# Laser_Sign_Remote.net
KiCad netlist of a schematic drawn in EasyEDA
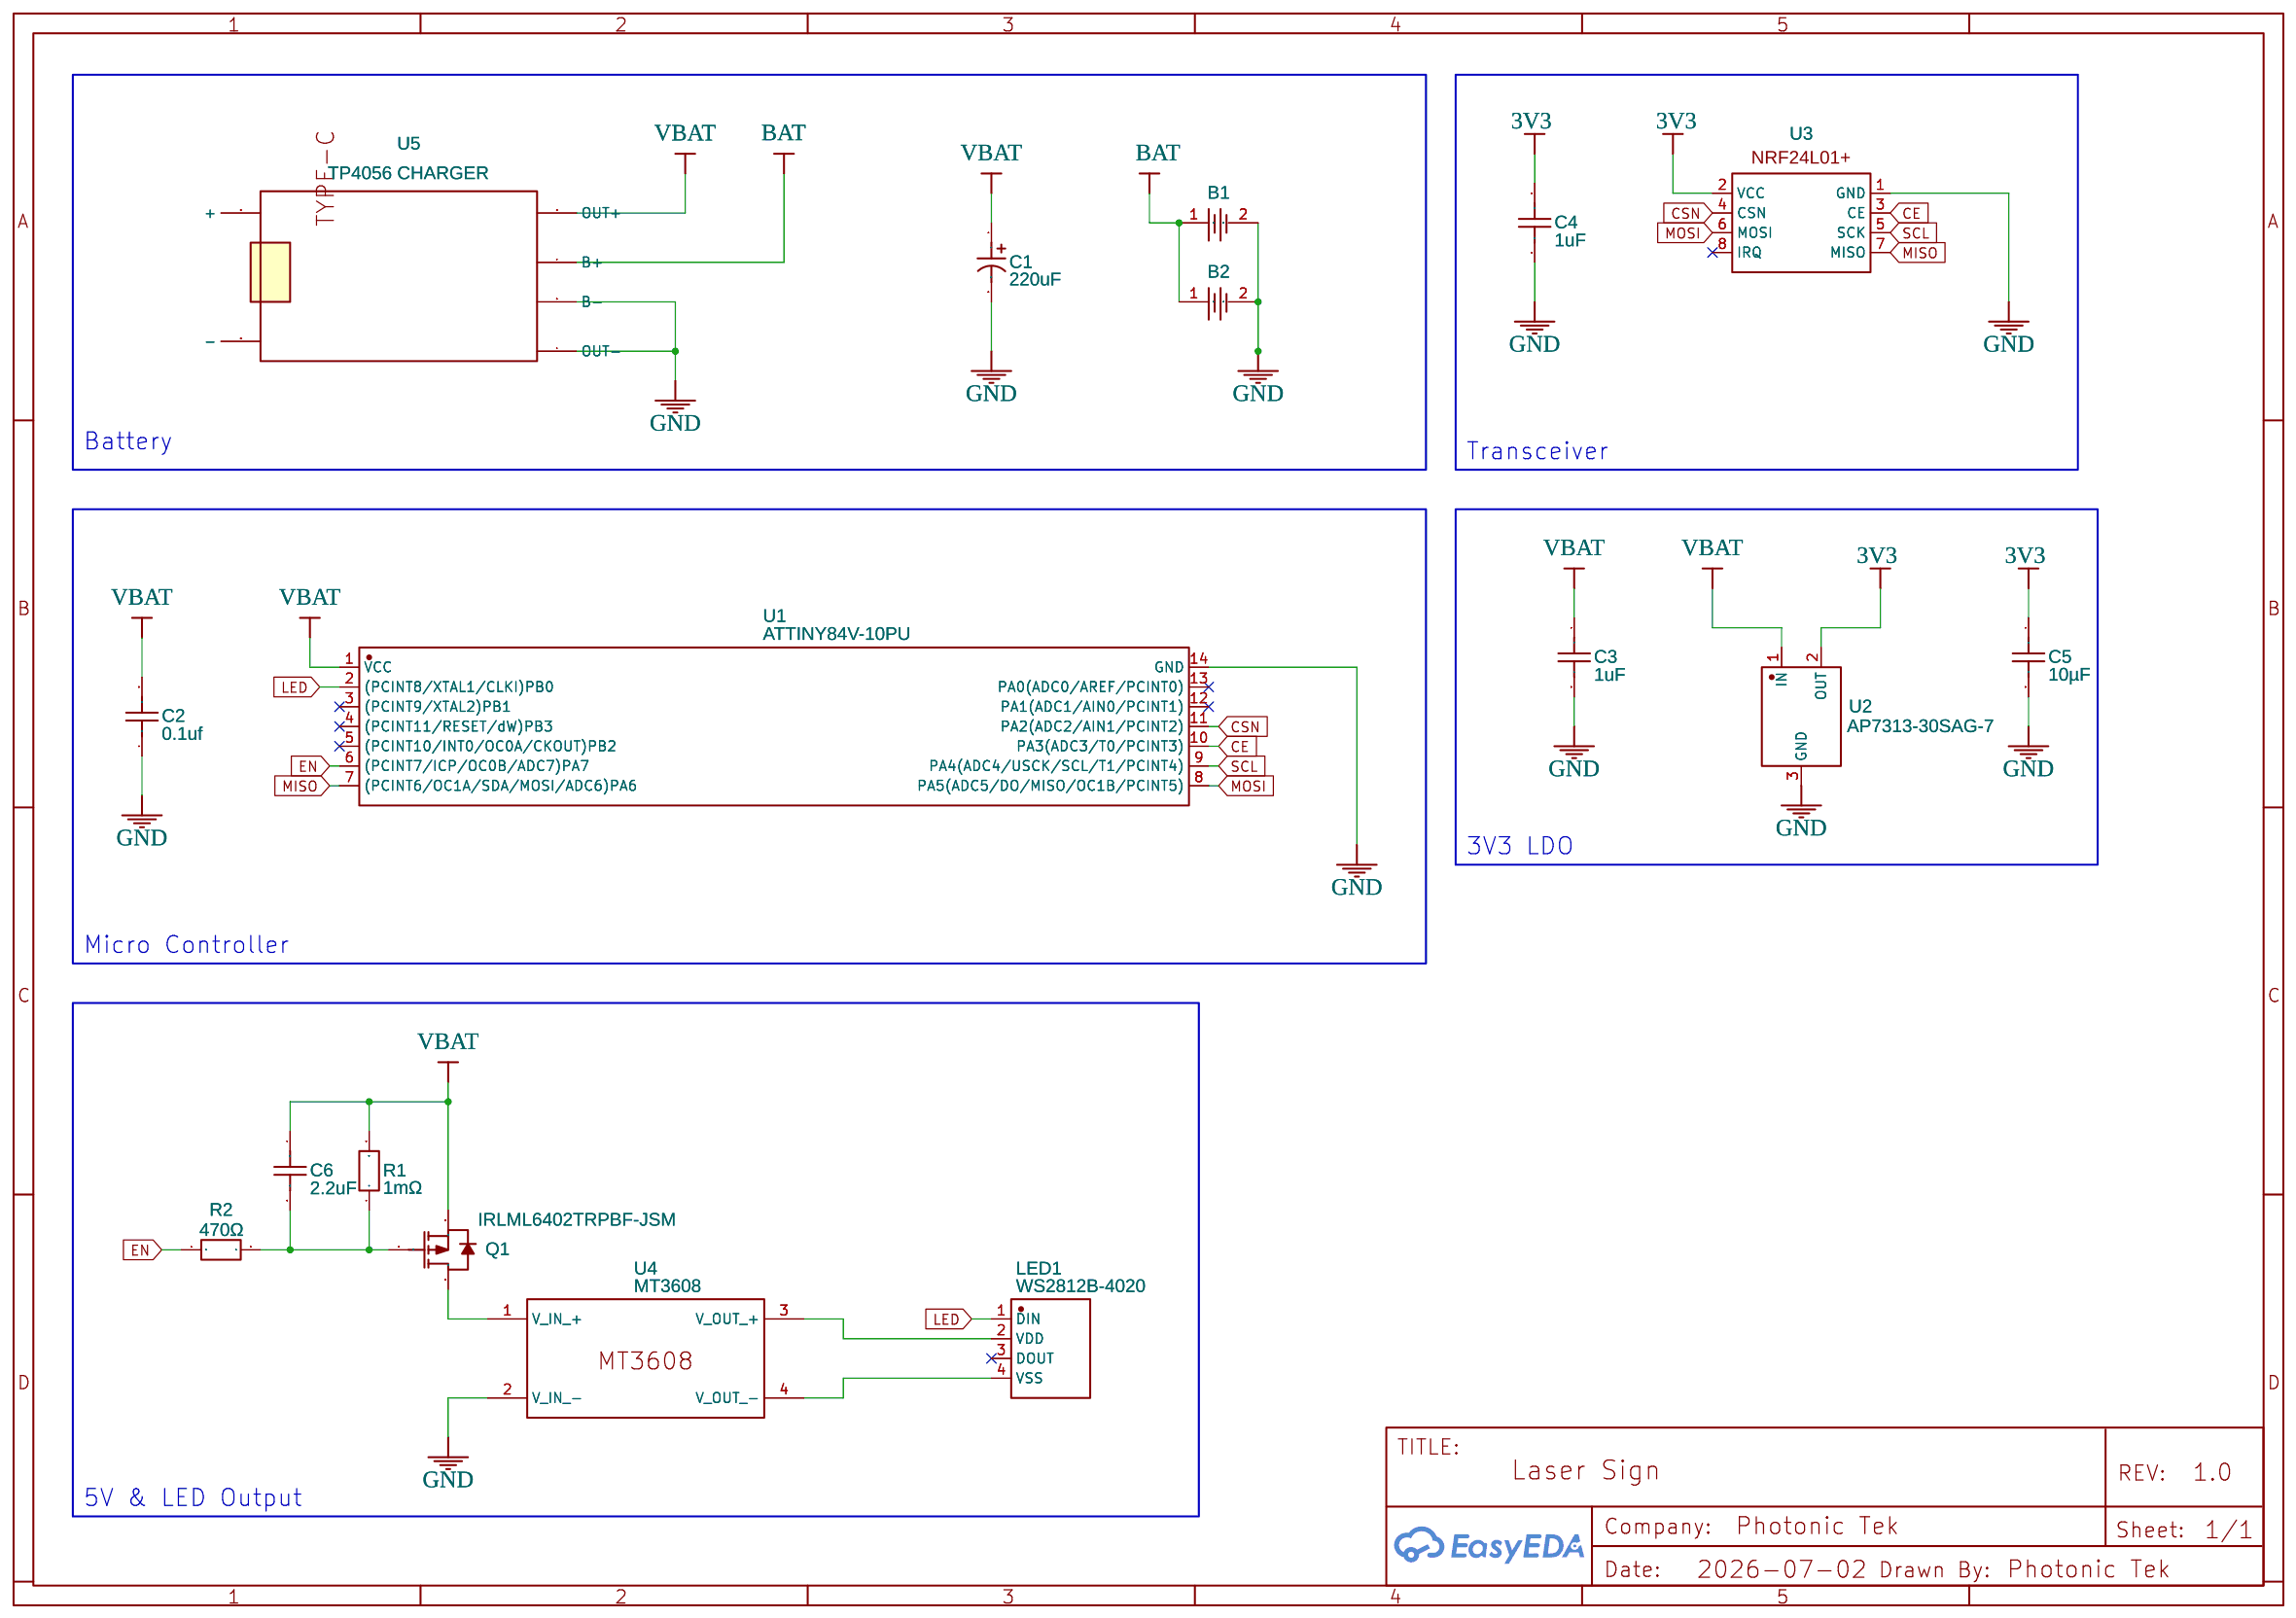
[diagram p0: Sheet_1]
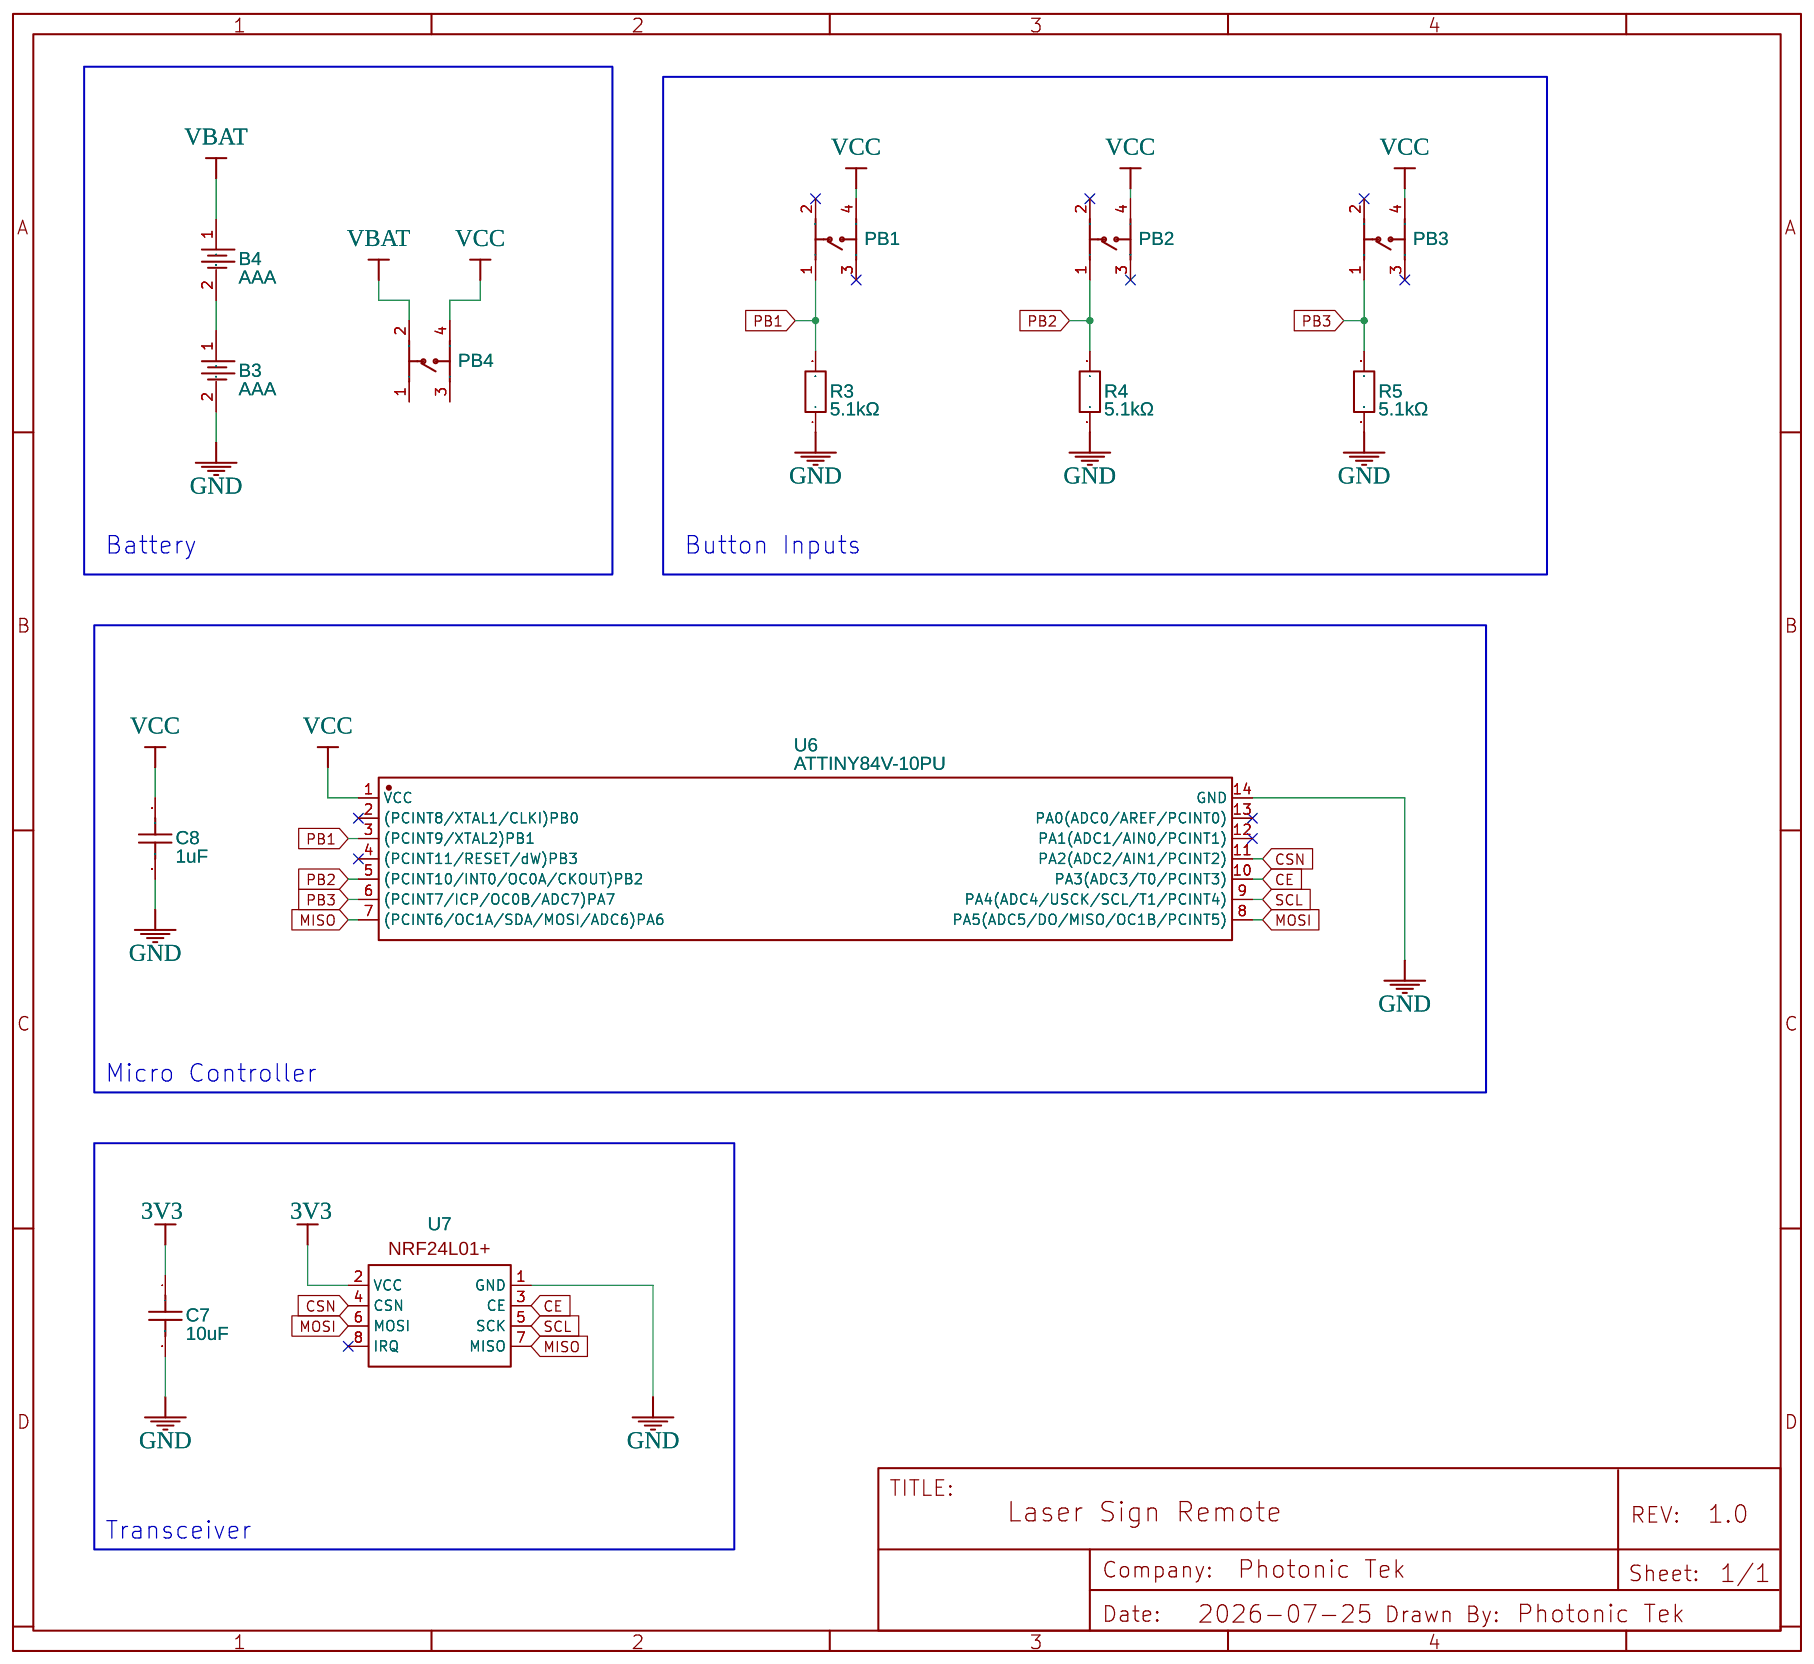
[diagram p1: Sheet_2]

(export (version "E")
  (design (tool "Eeschema 10.0.6"))
  (components
    (comp (ref "B1")
      (value "CR1220-2")
      (fields (field (name "Manufacturer") "Q&J"))
      (libsource (lib "") (part "CR1220-2"))
    )
    (comp (ref "B2")
      (value "CR1220-2")
      (fields (field (name "Manufacturer") "Q&J"))
      (libsource (lib "") (part "CR1220-2"))
    )
    (comp (ref "C1")
      (value "220uF")
      (fields (field (name "Manufacturer Part") "ERG50V220M10X13") (field (name "Manufacturer") "JIERR(捷而瑞)"))
      (libsource (lib "") (part "ERG50V220M10X13"))
    )
    (comp (ref "C2") (value "0.1uf") (libsource (lib "") (part "GE CERAMIC CAPACITOR")))
    (comp (ref "C3")
      (value "1uF")
      (fields (field (name "Manufacturer Part") "08053C105JAT2A") (field (name "Manufacturer") "KYOCERA AVX"))
      (libsource (lib "") (part "08053C105JAT2A"))
    )
    (comp (ref "C4")
      (value "1uF")
      (fields (field (name "Manufacturer Part") "08053C105JAT2A") (field (name "Manufacturer") "KYOCERA AVX"))
      (libsource (lib "") (part "08053C105JAT2A"))
    )
    (comp (ref "C5")
      (value "10µF")
      (fields
        (field (name "Manufacturer Part") "CL10A106MA8NRNC")
        (field (name "Manufacturer") "Samsung Electro-Mechanics")
      )
      (libsource (lib "") (part "CL10A106MA8NRNC"))
    )
    (comp (ref "C6")
      (value "2.2uF")
      (fields (field (name "Manufacturer Part") "08053C105JAT2A") (field (name "Manufacturer") "KYOCERA AVX"))
      (libsource (lib "") (part "08053C105JAT2A"))
    )
    (comp (ref "LED1")
      (value "WS2812B-4020")
      (fields (field (name "Manufacturer") "worldsemi"))
      (libsource (lib "") (part "WS2812B-4020"))
    )
    (comp (ref "Q1")
      (value "IRLML6402TRPBF-JSM")
      (fields (field (name "Manufacturer") "JSMSEMI(杰盛微)"))
      (libsource (lib "") (part "IRLML6402TRPBF-JSM"))
    )
    (comp (ref "R1")
      (value "1mΩ")
      (fields (field (name "Manufacturer Part") "TP810PW10K0JE") (field (name "Manufacturer") "Ohmite"))
      (libsource (lib "") (part "TP810PW10K0JE"))
    )
    (comp (ref "R2")
      (value "470Ω")
      (fields (field (name "Manufacturer Part") "TP810PW10K0JE") (field (name "Manufacturer") "Ohmite"))
      (libsource (lib "") (part "TP810PW10K0JE_1"))
    )
    (comp (ref "U1") (value "ATTINY84V-10PU") (libsource (lib "") (part "ATTINY84V-10PU")))
    (comp (ref "U2")
      (value "AP7313-30SAG-7")
      (fields (field (name "Manufacturer") "DIODES(美台)"))
      (libsource (lib "") (part "AP7313-30SAG-7"))
    )
    (comp (ref "U3") (value "NRF24L01+") (libsource (lib "") (part "NRF24L01+")))
    (comp (ref "U4") (value "MT3608") (libsource (lib "") (part "MT3608")))
    (comp (ref "U5")
      (value "TP4056 CHARGER")
      (fields (field (name "Manufacturer Part") "TP4056"))
      (libsource (lib "") (part "TP4056 CHARGING MODDULE"))
    )
    (comp (ref "B3")
      (value "AAA")
      (fields (field (name "Manufacturer Part") "CR1220-2") (field (name "Manufacturer") "Q&J"))
      (libsource (lib "") (part "CR1220-2"))
    )
    (comp (ref "B4")
      (value "AAA")
      (fields (field (name "Manufacturer Part") "CR1220-2") (field (name "Manufacturer") "Q&J"))
      (libsource (lib "") (part "CR1220-2"))
    )
    (comp (ref "C7")
      (value "10uF")
      (fields (field (name "Manufacturer Part") "08053C105JAT2A") (field (name "Manufacturer") "KYOCERA AVX"))
      (libsource (lib "") (part "08053C105JAT2A"))
    )
    (comp (ref "C8")
      (value "1uF")
      (fields (field (name "Manufacturer Part") "08053C105JAT2A") (field (name "Manufacturer") "KYOCERA AVX"))
      (libsource (lib "") (part "08053C105JAT2A"))
    )
    (comp (ref "PB1")
      (value "TSC005A2526B")
      (fields (field (name "Manufacturer") "BZCN(博众电气)"))
      (libsource (lib "") (part "TSC005A2526B"))
    )
    (comp (ref "PB2")
      (value "TSC005A2526B")
      (fields (field (name "Manufacturer") "BZCN(博众电气)"))
      (libsource (lib "") (part "TSC005A2526B"))
    )
    (comp (ref "PB3")
      (value "TSC005A2526B")
      (fields (field (name "Manufacturer") "BZCN(博众电气)"))
      (libsource (lib "") (part "TSC005A2526B"))
    )
    (comp (ref "PB4")
      (value "TSC005A2526B")
      (fields (field (name "Manufacturer") "BZCN(博众电气)"))
      (libsource (lib "") (part "TSC005A2526B"))
    )
    (comp (ref "R3")
      (value "5.1kΩ")
      (fields (field (name "Manufacturer Part") "ERJP06J512V") (field (name "Manufacturer") "PANASONIC(松下)"))
      (libsource (lib "") (part "ERJP06J512V"))
    )
    (comp (ref "R4")
      (value "5.1kΩ")
      (fields (field (name "Manufacturer Part") "ERJP06J512V") (field (name "Manufacturer") "PANASONIC(松下)"))
      (libsource (lib "") (part "ERJP06J512V"))
    )
    (comp (ref "R5")
      (value "5.1kΩ")
      (fields (field (name "Manufacturer Part") "ERJP06J512V") (field (name "Manufacturer") "PANASONIC(松下)"))
      (libsource (lib "") (part "ERJP06J512V"))
    )
    (comp (ref "U6") (value "ATTINY84V-10PU") (libsource (lib "") (part "ATTINY84V-10PU")))
    (comp (ref "U7") (value "NRF24L01+") (libsource (lib "") (part "NRF24L01+")))
  )
  (nets
    (net (code "1") (name "3V3") (class "Default")
      (node (ref "C4") (pin "1") (pinfunction "1_1") (pintype "unspecified"))
      (node (ref "C5") (pin "1") (pinfunction "1_1") (pintype "unspecified"))
      (node (ref "C7") (pin "1") (pinfunction "1_1") (pintype "unspecified"))
      (node (ref "U2") (pin "2") (pinfunction "OUT_2") (pintype "unspecified"))
      (node (ref "U3") (pin "2") (pinfunction "VCC_2") (pintype "unspecified"))
      (node (ref "U7") (pin "2") (pinfunction "VCC_2") (pintype "unspecified"))
    )
    (net (code "2") (name "BAT") (class "Default")
      (node (ref "B1") (pin "1") (pinfunction "1_1") (pintype "input"))
      (node (ref "B2") (pin "1") (pinfunction "1_1") (pintype "input"))
    )
    (net (code "3") (name "CE") (class "Default")
      (node (ref "U1") (pin "10") (pinfunction "PA3(ADC3/T0/PCINT3)_10") (pintype "unspecified"))
      (node (ref "U3") (pin "3") (pinfunction "CE_3") (pintype "unspecified"))
      (node (ref "U6") (pin "10") (pinfunction "PA3(ADC3/T0/PCINT3)_10") (pintype "unspecified"))
      (node (ref "U7") (pin "3") (pinfunction "CE_3") (pintype "unspecified"))
    )
    (net (code "4") (name "CSN") (class "Default")
      (node (ref "U1") (pin "11") (pinfunction "PA2(ADC2/AIN1/PCINT2)_11") (pintype "unspecified"))
      (node (ref "U3") (pin "4") (pinfunction "CSN_4") (pintype "unspecified"))
      (node (ref "U6") (pin "11") (pinfunction "PA2(ADC2/AIN1/PCINT2)_11") (pintype "unspecified"))
      (node (ref "U7") (pin "4") (pinfunction "CSN_4") (pintype "unspecified"))
    )
    (net (code "5") (name "EN") (class "Default")
      (node (ref "R2") (pin "1") (pinfunction "1_1") (pintype "unspecified"))
      (node (ref "U1") (pin "6") (pinfunction "(PCINT7/ICP/OC0B/ADC7)PA7_6") (pintype "unspecified"))
    )
    (net (code "6") (name "GND") (class "Default")
      (node (ref "B1") (pin "2") (pinfunction "2_2") (pintype "input"))
      (node (ref "B2") (pin "2") (pinfunction "2_2") (pintype "input"))
      (node (ref "B3") (pin "2") (pinfunction "2_2") (pintype "input"))
      (node (ref "C1") (pin "2") (pinfunction "2_2") (pintype "input"))
      (node (ref "C2") (pin "1") (pinfunction "1_1") (pintype "unspecified"))
      (node (ref "C3") (pin "2") (pinfunction "2_2") (pintype "unspecified"))
      (node (ref "C4") (pin "2") (pinfunction "2_2") (pintype "unspecified"))
      (node (ref "C5") (pin "2") (pinfunction "2_2") (pintype "unspecified"))
      (node (ref "C7") (pin "2") (pinfunction "2_2") (pintype "unspecified"))
      (node (ref "C8") (pin "2") (pinfunction "2_2") (pintype "unspecified"))
      (node (ref "R3") (pin "1") (pinfunction "1_1") (pintype "unspecified"))
      (node (ref "R4") (pin "1") (pinfunction "1_1") (pintype "unspecified"))
      (node (ref "R5") (pin "1") (pinfunction "1_1") (pintype "unspecified"))
      (node (ref "U1") (pin "14") (pinfunction "GND_14") (pintype "unspecified"))
      (node (ref "U2") (pin "3") (pinfunction "GND_3") (pintype "unspecified"))
      (node (ref "U3") (pin "1") (pinfunction "GND_1") (pintype "unspecified"))
      (node (ref "U4") (pin "2") (pinfunction "V_IN_-_2") (pintype "unspecified"))
      (node (ref "U6") (pin "14") (pinfunction "GND_14") (pintype "unspecified"))
      (node (ref "U7") (pin "1") (pinfunction "GND_1") (pintype "unspecified"))
    )
    (net (code "7") (name "LED") (class "Default")
      (node (ref "LED1") (pin "1") (pinfunction "DIN_1") (pintype "unspecified"))
      (node (ref "U1") (pin "2") (pinfunction "(PCINT8/XTAL1/CLKI)PB0_2") (pintype "unspecified"))
    )
    (net (code "8") (name "MISO") (class "Default")
      (node (ref "U1") (pin "7") (pinfunction "(PCINT6/OC1A/SDA/MOSI/ADC6)PA6_7") (pintype "unspecified"))
      (node (ref "U3") (pin "7") (pinfunction "MISO_7") (pintype "unspecified"))
      (node (ref "U6") (pin "7") (pinfunction "(PCINT6/OC1A/SDA/MOSI/ADC6)PA6_7") (pintype "unspecified"))
      (node (ref "U7") (pin "7") (pinfunction "MISO_7") (pintype "unspecified"))
    )
    (net (code "9") (name "MOSI") (class "Default")
      (node (ref "U1") (pin "8") (pinfunction "PA5(ADC5/DO/MISO/OC1B/PCINT5)_8") (pintype "unspecified"))
      (node (ref "U3") (pin "6") (pinfunction "MOSI_6") (pintype "unspecified"))
      (node (ref "U6") (pin "8") (pinfunction "PA5(ADC5/DO/MISO/OC1B/PCINT5)_8") (pintype "unspecified"))
      (node (ref "U7") (pin "6") (pinfunction "MOSI_6") (pintype "unspecified"))
    )
    (net (code "10") (name "Net-(B3-Pad1)") (class "Default")
      (node (ref "B3") (pin "1") (pinfunction "1_1") (pintype "input"))
      (node (ref "B4") (pin "2") (pinfunction "2_2") (pintype "input"))
    )
    (net (code "11") (name "Net-(LED1-VDD)") (class "Default")
      (node (ref "LED1") (pin "2") (pinfunction "VDD_2") (pintype "unspecified"))
      (node (ref "U4") (pin "3") (pinfunction "V_OUT_+_3") (pintype "unspecified"))
    )
    (net (code "12") (name "Net-(LED1-VSS)") (class "Default")
      (node (ref "LED1") (pin "4") (pinfunction "VSS_4") (pintype "unspecified"))
      (node (ref "U4") (pin "4") (pinfunction "V_OUT_-_4") (pintype "unspecified"))
    )
    (net (code "13") (name "Net-(Q1-D)") (class "Default")
      (node (ref "Q1") (pin "3") (pinfunction "D_3") (pintype "unspecified"))
      (node (ref "U4") (pin "1") (pinfunction "V_IN_+_1") (pintype "unspecified"))
    )
    (net (code "14") (name "Net-(Q1-G)") (class "Default")
      (node (ref "C6") (pin "2") (pinfunction "2_2") (pintype "unspecified"))
      (node (ref "Q1") (pin "1") (pinfunction "G_1") (pintype "unspecified"))
      (node (ref "R1") (pin "1") (pinfunction "1_1") (pintype "unspecified"))
      (node (ref "R2") (pin "2") (pinfunction "2_2") (pintype "unspecified"))
    )
    (net (code "15") (name "PB1") (class "Default")
      (node (ref "PB1") (pin "1") (pinfunction "1_1") (pintype "unspecified"))
      (node (ref "R3") (pin "2") (pinfunction "2_2") (pintype "unspecified"))
      (node (ref "U6") (pin "3") (pinfunction "(PCINT9/XTAL2)PB1_3") (pintype "unspecified"))
    )
    (net (code "16") (name "PB2") (class "Default")
      (node (ref "PB2") (pin "1") (pinfunction "1_1") (pintype "unspecified"))
      (node (ref "R4") (pin "2") (pinfunction "2_2") (pintype "unspecified"))
      (node (ref "U6") (pin "5") (pinfunction "(PCINT10/INT0/OC0A/CKOUT)PB2_5") (pintype "unspecified"))
    )
    (net (code "17") (name "PB3") (class "Default")
      (node (ref "PB3") (pin "1") (pinfunction "1_1") (pintype "unspecified"))
      (node (ref "R5") (pin "2") (pinfunction "2_2") (pintype "unspecified"))
      (node (ref "U6") (pin "6") (pinfunction "(PCINT7/ICP/OC0B/ADC7)PA7_6") (pintype "unspecified"))
    )
    (net (code "18") (name "SCL") (class "Default")
      (node (ref "U1") (pin "9") (pinfunction "PA4(ADC4/USCK/SCL/T1/PCINT4)_9") (pintype "unspecified"))
      (node (ref "U3") (pin "5") (pinfunction "SCK_5") (pintype "unspecified"))
      (node (ref "U6") (pin "9") (pinfunction "PA4(ADC4/USCK/SCL/T1/PCINT4)_9") (pintype "unspecified"))
      (node (ref "U7") (pin "5") (pinfunction "SCK_5") (pintype "unspecified"))
    )
    (net (code "19") (name "VBAT") (class "Default")
      (node (ref "B4") (pin "1") (pinfunction "1_1") (pintype "input"))
      (node (ref "C1") (pin "1") (pinfunction "1_1") (pintype "input"))
      (node (ref "C2") (pin "2") (pinfunction "2_2") (pintype "unspecified"))
      (node (ref "C3") (pin "1") (pinfunction "1_1") (pintype "unspecified"))
      (node (ref "C6") (pin "1") (pinfunction "1_1") (pintype "unspecified"))
      (node (ref "PB4") (pin "2") (pinfunction "2_2") (pintype "unspecified"))
      (node (ref "Q1") (pin "2") (pinfunction "S_2") (pintype "unspecified"))
      (node (ref "R1") (pin "2") (pinfunction "2_2") (pintype "unspecified"))
      (node (ref "U1") (pin "1") (pinfunction "VCC_1") (pintype "unspecified"))
      (node (ref "U2") (pin "1") (pinfunction "IN_1") (pintype "unspecified"))
    )
    (net (code "20") (name "VCC") (class "Default")
      (node (ref "C8") (pin "1") (pinfunction "1_1") (pintype "unspecified"))
      (node (ref "PB1") (pin "4") (pinfunction "4_4") (pintype "unspecified"))
      (node (ref "PB2") (pin "4") (pinfunction "4_4") (pintype "unspecified"))
      (node (ref "PB3") (pin "4") (pinfunction "4_4") (pintype "unspecified"))
      (node (ref "PB4") (pin "4") (pinfunction "4_4") (pintype "unspecified"))
      (node (ref "U6") (pin "1") (pinfunction "VCC_1") (pintype "unspecified"))
    )
    (net (code "21") (name "unconnected-(LED1-DOUT-Pad3)") (class "Default")
      (node (ref "LED1") (pin "3") (pinfunction "DOUT_3") (pintype "unspecified+no_connect"))
    )
    (net (code "22") (name "unconnected-(PB1-Pad2)") (class "Default")
      (node (ref "PB1") (pin "2") (pinfunction "2_2") (pintype "unspecified+no_connect"))
    )
    (net (code "23") (name "unconnected-(PB1-Pad3)") (class "Default")
      (node (ref "PB1") (pin "3") (pinfunction "3_3") (pintype "unspecified+no_connect"))
    )
    (net (code "24") (name "unconnected-(PB2-Pad2)") (class "Default")
      (node (ref "PB2") (pin "2") (pinfunction "2_2") (pintype "unspecified+no_connect"))
    )
    (net (code "25") (name "unconnected-(PB2-Pad3)") (class "Default")
      (node (ref "PB2") (pin "3") (pinfunction "3_3") (pintype "unspecified+no_connect"))
    )
    (net (code "26") (name "unconnected-(PB3-Pad2)") (class "Default")
      (node (ref "PB3") (pin "2") (pinfunction "2_2") (pintype "unspecified+no_connect"))
    )
    (net (code "27") (name "unconnected-(PB3-Pad3)") (class "Default")
      (node (ref "PB3") (pin "3") (pinfunction "3_3") (pintype "unspecified+no_connect"))
    )
    (net (code "28") (name "unconnected-(PB4-Pad1)") (class "Default")
      (node (ref "PB4") (pin "1") (pinfunction "1_1") (pintype "unspecified"))
    )
    (net (code "29") (name "unconnected-(PB4-Pad3)") (class "Default")
      (node (ref "PB4") (pin "3") (pinfunction "3_3") (pintype "unspecified"))
    )
    (net (code "30") (name "unconnected-(U1-(PCINT9{slash}XTAL2)PB1-Pad3)") (class "Default")
      (node (ref "U1") (pin "3") (pinfunction "(PCINT9/XTAL2)PB1_3") (pintype "unspecified+no_connect"))
    )
    (net (code "31") (name "unconnected-(U1-(PCINT10{slash}INT0{slash}OC0A{slash}CKOUT)PB2-Pad5)") (class "Default")
      (node (ref "U1") (pin "5") (pinfunction "(PCINT10/INT0/OC0A/CKOUT)PB2_5") (pintype "unspecified+no_connect"))
    )
    (net (code "32") (name "unconnected-(U1-(PCINT11{slash}RESET{slash}dW)PB3-Pad4)") (class "Default")
      (node (ref "U1") (pin "4") (pinfunction "(PCINT11/RESET/dW)PB3_4") (pintype "unspecified+no_connect"))
    )
    (net (code "33") (name "unconnected-(U1-PA0(ADC0{slash}AREF{slash}PCINT0)-Pad13)") (class "Default")
      (node (ref "U1") (pin "13") (pinfunction "PA0(ADC0/AREF/PCINT0)_13") (pintype "unspecified+no_connect"))
    )
    (net (code "34") (name "unconnected-(U1-PA1(ADC1{slash}AIN0{slash}PCINT1)-Pad12)") (class "Default")
      (node (ref "U1") (pin "12") (pinfunction "PA1(ADC1/AIN0/PCINT1)_12") (pintype "unspecified+no_connect"))
    )
    (net (code "35") (name "unconnected-(U3-IRQ-Pad8)") (class "Default")
      (node (ref "U3") (pin "8") (pinfunction "IRQ_8") (pintype "unspecified+no_connect"))
    )
    (net (code "36") (name "unconnected-(U5-+-Pad5)") (class "Default")
      (node (ref "U5") (pin "5") (pinfunction "+_5") (pintype "unspecified"))
    )
    (net (code "37") (name "unconnected-(U5---Pad6)") (class "Default")
      (node (ref "U5") (pin "6") (pinfunction "-_6") (pintype "unspecified"))
    )
    (net (code "38") (name "unconnected-(U5-B+-Pad1)") (class "Default")
      (node (ref "U5") (pin "1") (pinfunction "B+_1") (pintype "unspecified"))
    )
    (net (code "39") (name "unconnected-(U5-B--Pad2)") (class "Default")
      (node (ref "U5") (pin "2") (pinfunction "B-_2") (pintype "unspecified"))
    )
    (net (code "40") (name "unconnected-(U5-OUT+-Pad3)") (class "Default")
      (node (ref "U5") (pin "3") (pinfunction "OUT+_3") (pintype "unspecified"))
    )
    (net (code "41") (name "unconnected-(U5-OUT--Pad4)") (class "Default")
      (node (ref "U5") (pin "4") (pinfunction "OUT-_4") (pintype "unspecified"))
    )
    (net (code "42") (name "unconnected-(U6-(PCINT8{slash}XTAL1{slash}CLKI)PB0-Pad2)") (class "Default")
      (node (ref "U6") (pin "2") (pinfunction "(PCINT8/XTAL1/CLKI)PB0_2") (pintype "unspecified+no_connect"))
    )
    (net (code "43") (name "unconnected-(U6-(PCINT11{slash}RESET{slash}dW)PB3-Pad4)") (class "Default")
      (node (ref "U6") (pin "4") (pinfunction "(PCINT11/RESET/dW)PB3_4") (pintype "unspecified+no_connect"))
    )
    (net (code "44") (name "unconnected-(U6-PA0(ADC0{slash}AREF{slash}PCINT0)-Pad13)") (class "Default")
      (node (ref "U6") (pin "13") (pinfunction "PA0(ADC0/AREF/PCINT0)_13") (pintype "unspecified+no_connect"))
    )
    (net (code "45") (name "unconnected-(U6-PA1(ADC1{slash}AIN0{slash}PCINT1)-Pad12)") (class "Default")
      (node (ref "U6") (pin "12") (pinfunction "PA1(ADC1/AIN0/PCINT1)_12") (pintype "unspecified+no_connect"))
    )
    (net (code "46") (name "unconnected-(U7-IRQ-Pad8)") (class "Default")
      (node (ref "U7") (pin "8") (pinfunction "IRQ_8") (pintype "unspecified+no_connect"))
    )
  )
)
